# SmartSwitch2_0.net
KiCad netlist of a schematic drawn in Altium Designer
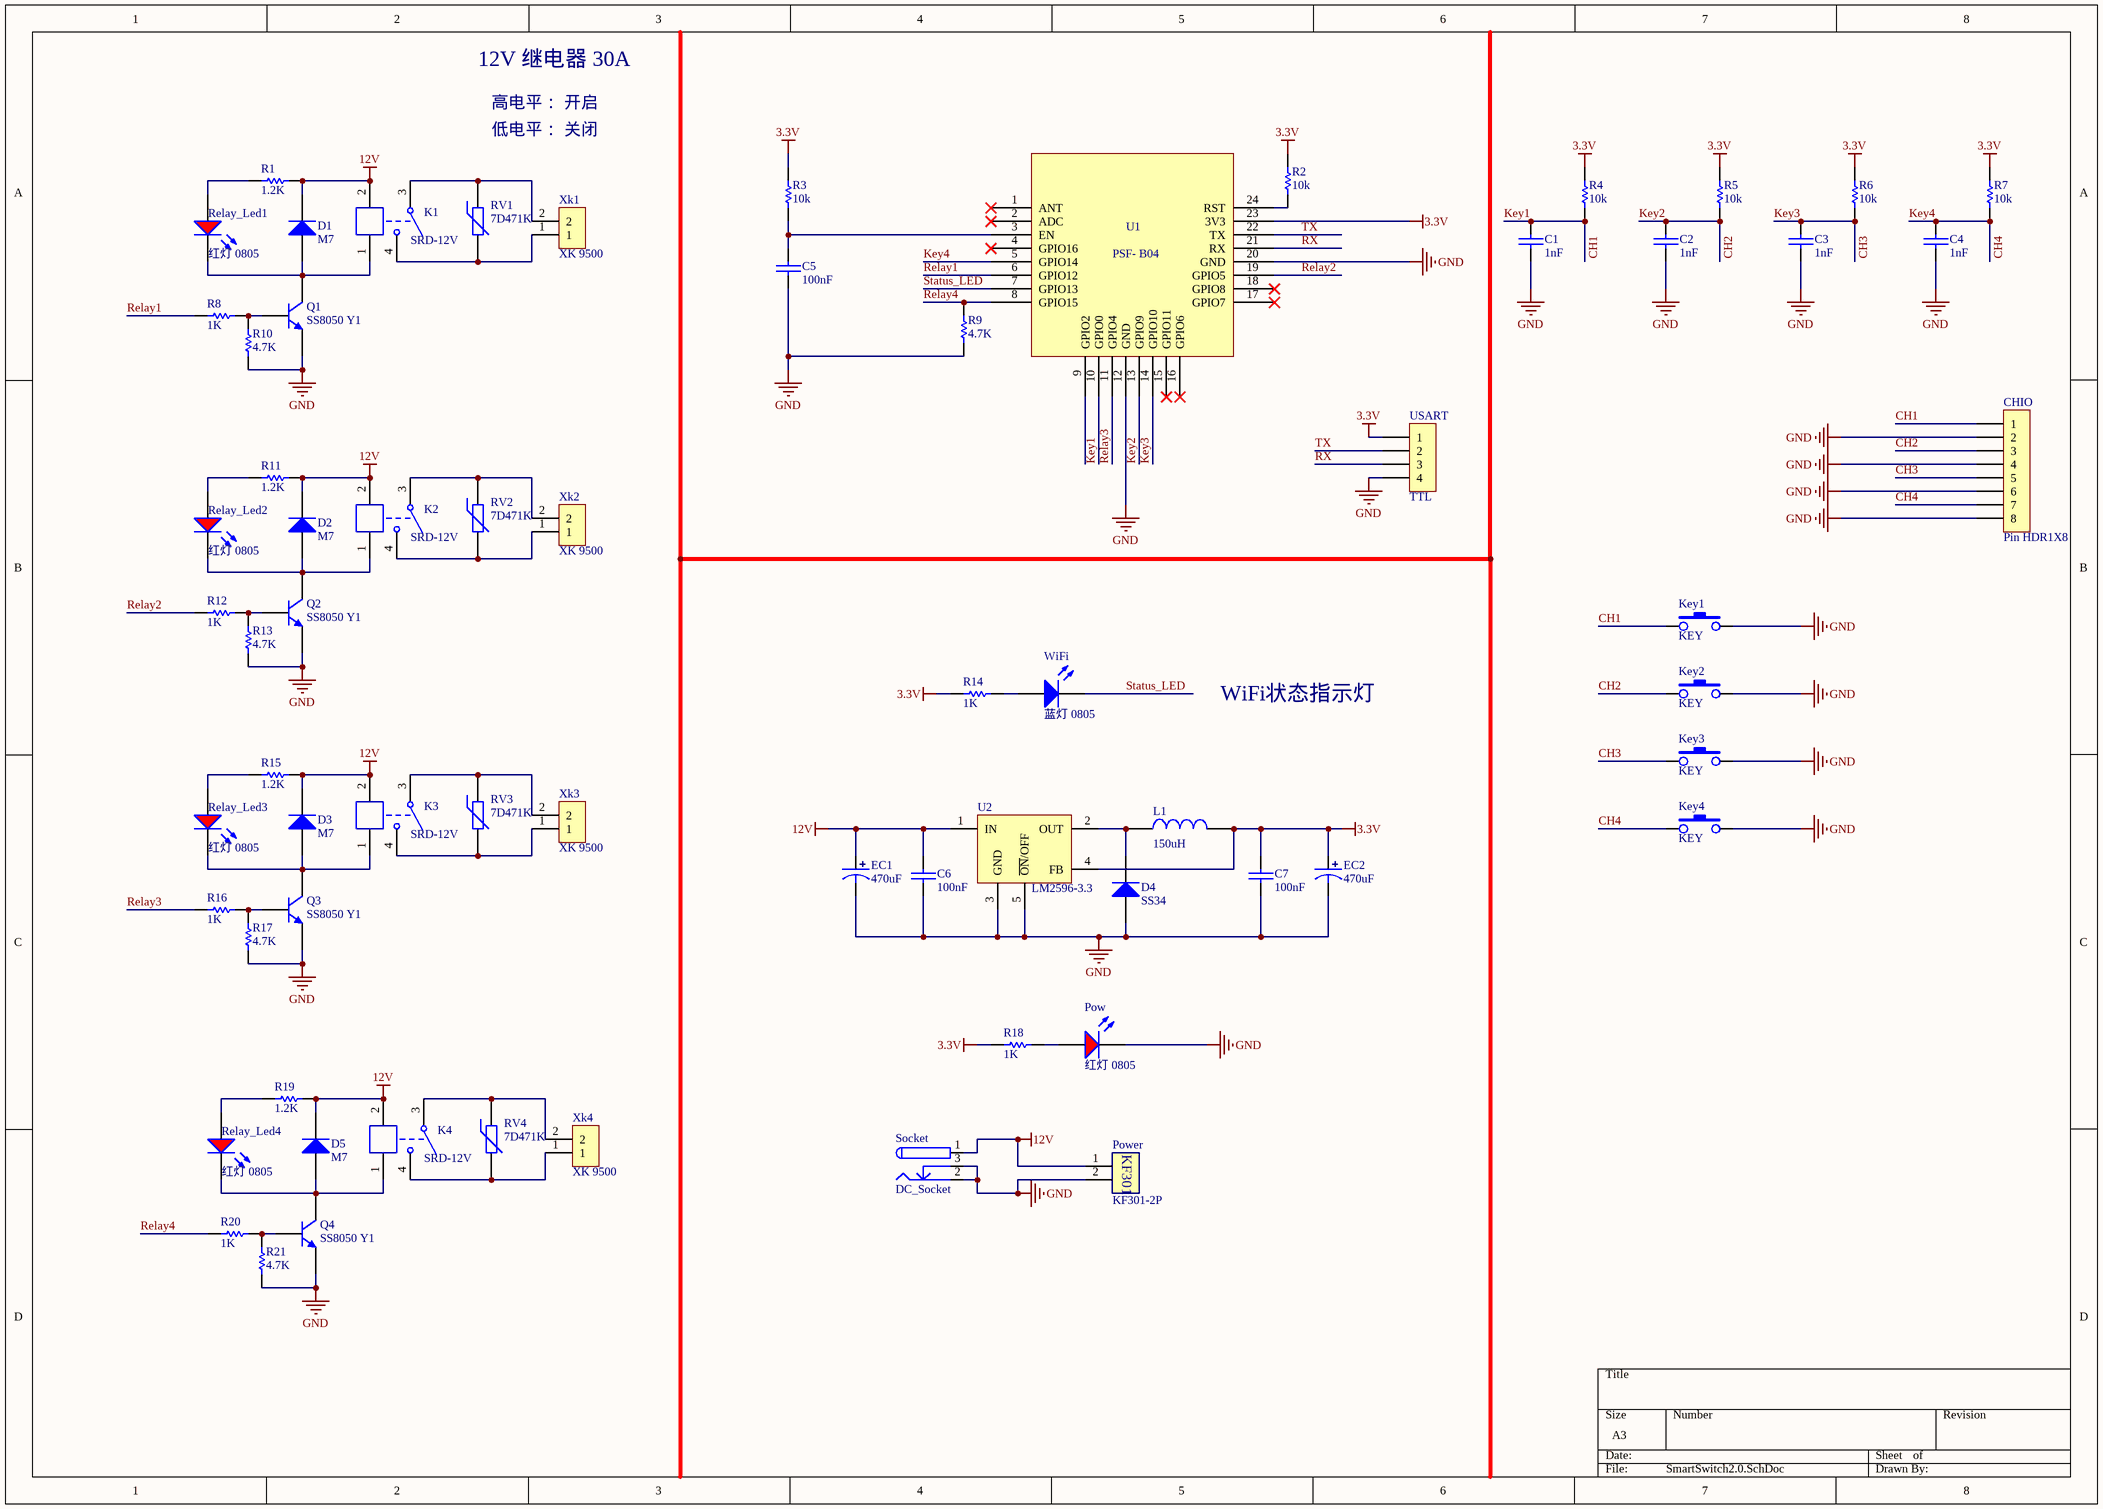
[diagram p0: SmartSwitch2.0.SchDoc]

(export (version "E")
  (design (tool "Eeschema 10.0.6"))
  (components
    (comp (ref "C1")
      (value "1nF")
      (footprint "0603C")
      (description "无极性电容")
      (libsource (lib "电容") (part "CAP"))
    )
    (comp (ref "C2")
      (value "1nF")
      (footprint "0603C")
      (description "无极性电容")
      (libsource (lib "电容") (part "CAP"))
    )
    (comp (ref "C3")
      (value "1nF")
      (footprint "0603C")
      (description "无极性电容")
      (libsource (lib "电容") (part "CAP"))
    )
    (comp (ref "C4")
      (value "1nF")
      (footprint "0603C")
      (description "无极性电容")
      (libsource (lib "电容") (part "CAP"))
    )
    (comp (ref "C5")
      (value "100nF")
      (footprint "0603C")
      (description "无极性电容")
      (libsource (lib "电容") (part "CAP"))
    )
    (comp (ref "C6")
      (value "100nF")
      (footprint "0603C")
      (description "无极性电容")
      (libsource (lib "电容") (part "CAP"))
    )
    (comp (ref "C7")
      (value "100nF")
      (footprint "0603C")
      (description "无极性电容")
      (libsource (lib "电容") (part "CAP"))
    )
    (comp (ref "CHIO")
      (value "Pin HDR1X8")
      (footprint "Pin HDR1X8/2.54mm-S")
      (libsource (lib "排针") (part "Pin HDR1X8"))
    )
    (comp (ref "D1")
      (value "M7")
      (footprint "SMA(DO-214AC)_S1")
      (description "二极管")
      (libsource (lib "Miscellaneous Devices LC") (part "SMA(DO-214AC) M7"))
    )
    (comp (ref "D2")
      (value "M7")
      (footprint "SMA(DO-214AC)_S1")
      (description "二极管")
      (libsource (lib "Miscellaneous Devices LC") (part "SMA(DO-214AC) M7"))
    )
    (comp (ref "D3")
      (value "M7")
      (footprint "SMA(DO-214AC)_S1")
      (description "二极管")
      (libsource (lib "Miscellaneous Devices LC") (part "SMA(DO-214AC) M7"))
    )
    (comp (ref "D4")
      (value "SS34")
      (footprint "SMA(DO-214AC)_S1")
      (description "二极管")
      (libsource (lib "Miscellaneous Devices LC") (part "SMA(DO-214AC) SS54"))
    )
    (comp (ref "D5")
      (value "M7")
      (footprint "SMA(DO-214AC)_S1")
      (description "二极管")
      (libsource (lib "Miscellaneous Devices LC") (part "SMA(DO-214AC) M7"))
    )
    (comp (ref "EC1")
      (value "470uF")
      (footprint "SMD-EC8X8X10")
      (description "贴片电解电容")
      (libsource (lib "电容") (part "SMD_ECAP"))
    )
    (comp (ref "EC2")
      (value "470uF")
      (footprint "SMD-EC8X8X10")
      (description "贴片电解电容")
      (libsource (lib "电容") (part "SMD_ECAP"))
    )
    (comp (ref "K1")
      (value "SRD-12V")
      (footprint "SLA-xxVDC-SL-A")
      (description "12V一组常开")
      (libsource (lib "继电器") (part "SLA-12VDC-SL-A"))
    )
    (comp (ref "K2")
      (value "SRD-12V")
      (footprint "SLA-xxVDC-SL-A")
      (description "12V一组常开")
      (libsource (lib "继电器") (part "SLA-12VDC-SL-A"))
    )
    (comp (ref "K3")
      (value "SRD-12V")
      (footprint "SLA-xxVDC-SL-A")
      (description "12V一组常开")
      (libsource (lib "继电器") (part "SLA-12VDC-SL-A"))
    )
    (comp (ref "K4")
      (value "SRD-12V")
      (footprint "SLA-xxVDC-SL-A")
      (description "12V一组常开")
      (libsource (lib "继电器") (part "SLA-12VDC-SL-A"))
    )
    (comp (ref "Key1") (value "KEY") (footprint "DIP-6X6X4.3") (libsource (lib "轻触开关") (part "KEY")))
    (comp (ref "Key2") (value "KEY") (footprint "DIP-6X6X4.3") (libsource (lib "轻触开关") (part "KEY")))
    (comp (ref "Key3") (value "KEY") (footprint "DIP-6X6X4.3") (libsource (lib "轻触开关") (part "KEY")))
    (comp (ref "Key4") (value "KEY") (footprint "DIP-6X6X4.3") (libsource (lib "轻触开关") (part "KEY")))
    (comp (ref "L1")
      (value "150uH")
      (footprint "PK0810")
      (description "INDUCTOR")
      (libsource (lib "电感") (part "INDUCTOR"))
    )
    (comp (ref "Pow")
      (value "红灯 0805")
      (footprint "0805_LED_S1")
      (description "发光二极管")
      (libsource (lib "Miscellaneous Devices LC") (part "0805 红灯"))
    )
    (comp (ref "Power")
      (value "KF301-2P")
      (footprint "KF301-5.0-2P")
      (libsource (lib "KF301") (part "KF301-2P"))
    )
    (comp (ref "Q1")
      (value "SS8050 Y1")
      (footprint "SOT-23(SOT-23-3)")
      (description "三极管")
      (libsource (lib "Miscellaneous Devices LC") (part "SOT-23 SS8050 Y1"))
    )
    (comp (ref "Q2")
      (value "SS8050 Y1")
      (footprint "SOT-23(SOT-23-3)")
      (description "三极管")
      (libsource (lib "Miscellaneous Devices LC") (part "SOT-23 SS8050 Y1"))
    )
    (comp (ref "Q3")
      (value "SS8050 Y1")
      (footprint "SOT-23(SOT-23-3)")
      (description "三极管")
      (libsource (lib "Miscellaneous Devices LC") (part "SOT-23 SS8050 Y1"))
    )
    (comp (ref "Q4")
      (value "SS8050 Y1")
      (footprint "SOT-23(SOT-23-3)")
      (description "三极管")
      (libsource (lib "Miscellaneous Devices LC") (part "SOT-23 SS8050 Y1"))
    )
    (comp (ref "R1") (value "1.2K") (footprint "0603R") (libsource (lib "电阻") (part "RES")))
    (comp (ref "R2") (value "10k") (footprint "0603R") (libsource (lib "电阻") (part "RES")))
    (comp (ref "R3") (value "10k") (footprint "0603R") (libsource (lib "电阻") (part "RES")))
    (comp (ref "R4") (value "10k") (footprint "0603R") (libsource (lib "电阻") (part "RES")))
    (comp (ref "R5") (value "10k") (footprint "0603R") (libsource (lib "电阻") (part "RES")))
    (comp (ref "R6") (value "10k") (footprint "0603R") (libsource (lib "电阻") (part "RES")))
    (comp (ref "R7") (value "10k") (footprint "0603R") (libsource (lib "电阻") (part "RES")))
    (comp (ref "R8") (value "1K") (footprint "0603R") (libsource (lib "电阻") (part "RES")))
    (comp (ref "R9") (value "4.7K") (footprint "0603R") (libsource (lib "电阻") (part "RES")))
    (comp (ref "R10") (value "4.7K") (footprint "0603R") (libsource (lib "电阻") (part "RES")))
    (comp (ref "R11") (value "1.2K") (footprint "0603R") (libsource (lib "电阻") (part "RES")))
    (comp (ref "R12") (value "1K") (footprint "0603R") (libsource (lib "电阻") (part "RES")))
    (comp (ref "R13") (value "4.7K") (footprint "0603R") (libsource (lib "电阻") (part "RES")))
    (comp (ref "R14") (value "1K") (footprint "0603R") (libsource (lib "电阻") (part "RES")))
    (comp (ref "R15") (value "1.2K") (footprint "0603R") (libsource (lib "电阻") (part "RES")))
    (comp (ref "R16") (value "1K") (footprint "0603R") (libsource (lib "电阻") (part "RES")))
    (comp (ref "R17") (value "4.7K") (footprint "0603R") (libsource (lib "电阻") (part "RES")))
    (comp (ref "R18") (value "1K") (footprint "0603R") (libsource (lib "电阻") (part "RES")))
    (comp (ref "R19") (value "1.2K") (footprint "0603R") (libsource (lib "电阻") (part "RES")))
    (comp (ref "R20") (value "1K") (footprint "0603R") (libsource (lib "电阻") (part "RES")))
    (comp (ref "R21") (value "4.7K") (footprint "0603R") (libsource (lib "电阻") (part "RES")))
    (comp (ref "Relay_Led1")
      (value "红灯 0805")
      (footprint "0805_LED_S1")
      (description "发光二极管")
      (libsource (lib "Miscellaneous Devices LC") (part "0805 红灯"))
    )
    (comp (ref "Relay_Led2")
      (value "红灯 0805")
      (footprint "0805_LED_S1")
      (description "发光二极管")
      (libsource (lib "Miscellaneous Devices LC") (part "0805 红灯"))
    )
    (comp (ref "Relay_Led3")
      (value "红灯 0805")
      (footprint "0805_LED_S1")
      (description "发光二极管")
      (libsource (lib "Miscellaneous Devices LC") (part "0805 红灯"))
    )
    (comp (ref "Relay_Led4")
      (value "红灯 0805")
      (footprint "0805_LED_S1")
      (description "发光二极管")
      (libsource (lib "Miscellaneous Devices LC") (part "0805 红灯"))
    )
    (comp (ref "RV1")
      (value "7D471K")
      (footprint "Varistor-7.5mm")
      (description "压敏电阻")
      (libsource (lib "电阻") (part "Varistor"))
    )
    (comp (ref "RV2")
      (value "7D471K")
      (footprint "Varistor-7.5mm")
      (description "压敏电阻")
      (libsource (lib "电阻") (part "Varistor"))
    )
    (comp (ref "RV3")
      (value "7D471K")
      (footprint "Varistor-7.5mm")
      (description "压敏电阻")
      (libsource (lib "电阻") (part "Varistor"))
    )
    (comp (ref "RV4")
      (value "7D471K")
      (footprint "Varistor-7.5mm")
      (description "压敏电阻")
      (libsource (lib "电阻") (part "Varistor"))
    )
    (comp (ref "Socket") (value "DC_Socket") (footprint "DC-005") (libsource (lib "电源插座") (part "DC_Socket")))
    (comp (ref "U1")
      (value "PSF- B04")
      (footprint "PSF- B04")
      (libsource (lib "my_Library") (part "PSF- B04"))
    )
    (comp (ref "U2")
      (value "LM2596-3.3")
      (footprint "TO263-5A")
      (description "DC降压芯片")
      (libsource (lib "电源芯片") (part "LM2596-3.3"))
    )
    (comp (ref "USART")
      (value "TTL")
      (footprint "Pin HDR1X4/2.54mm-S")
      (libsource (lib "排针") (part "Pin HDR1X4"))
    )
    (comp (ref "WiFi")
      (value "蓝灯 0805")
      (footprint "0805_LED_S1")
      (description "发光二极管")
      (libsource (lib "Miscellaneous Devices LC") (part "0805 蓝灯"))
    )
    (comp (ref "Xk1") (value "XK 9500") (footprint "XK 9500") (libsource (lib "my_Library") (part "XK 9500")))
    (comp (ref "Xk2") (value "XK 9500") (footprint "XK 9500") (libsource (lib "my_Library") (part "XK 9500")))
    (comp (ref "Xk3") (value "XK 9500") (footprint "XK 9500") (libsource (lib "my_Library") (part "XK 9500")))
    (comp (ref "Xk4") (value "XK 9500") (footprint "XK 9500") (libsource (lib "my_Library") (part "XK 9500")))
  )
  (nets
    (net (code "1") (name "/CH1") (class "Default")
      (node (ref "C1") (pin "2") (pinfunction "2_2") (pintype "passive"))
      (node (ref "CHIO") (pin "1") (pinfunction "1_1") (pintype "passive"))
      (node (ref "Key1") (pin "1") (pinfunction "1_1") (pintype "passive"))
      (node (ref "R4") (pin "2") (pinfunction "2_2") (pintype "passive"))
      (node (ref "U1") (pin "10") (pinfunction "GPIO0_10") (pintype "passive"))
    )
    (net (code "2") (name "/CH2") (class "Default")
      (node (ref "C2") (pin "2") (pinfunction "2_2") (pintype "passive"))
      (node (ref "CHIO") (pin "3") (pinfunction "3_3") (pintype "passive"))
      (node (ref "Key2") (pin "1") (pinfunction "1_1") (pintype "passive"))
      (node (ref "R5") (pin "2") (pinfunction "2_2") (pintype "passive"))
      (node (ref "U1") (pin "13") (pinfunction "GPIO9_13") (pintype "passive"))
    )
    (net (code "3") (name "/CH3") (class "Default")
      (node (ref "C3") (pin "2") (pinfunction "2_2") (pintype "passive"))
      (node (ref "CHIO") (pin "5") (pinfunction "5_5") (pintype "passive"))
      (node (ref "Key3") (pin "1") (pinfunction "1_1") (pintype "passive"))
      (node (ref "R6") (pin "2") (pinfunction "2_2") (pintype "passive"))
      (node (ref "U1") (pin "14") (pinfunction "GPIO10_14") (pintype "passive"))
    )
    (net (code "4") (name "/CH4") (class "Default")
      (node (ref "C4") (pin "2") (pinfunction "2_2") (pintype "passive"))
      (node (ref "CHIO") (pin "7") (pinfunction "7_7") (pintype "passive"))
      (node (ref "Key4") (pin "1") (pinfunction "1_1") (pintype "passive"))
      (node (ref "R7") (pin "2") (pinfunction "2_2") (pintype "passive"))
      (node (ref "U1") (pin "5") (pinfunction "GPIO14_5") (pintype "passive"))
    )
    (net (code "5") (name "/RX") (class "Default")
      (node (ref "U1") (pin "21") (pinfunction "RX_21") (pintype "passive"))
      (node (ref "USART") (pin "3") (pinfunction "3_3") (pintype "passive"))
    )
    (net (code "6") (name "/Relay1") (class "Default")
      (node (ref "R8") (pin "1") (pinfunction "1_1") (pintype "passive"))
      (node (ref "U1") (pin "6") (pinfunction "GPIO12_6") (pintype "passive"))
    )
    (net (code "7") (name "/Relay2") (class "Default")
      (node (ref "R12") (pin "1") (pinfunction "1_1") (pintype "passive"))
      (node (ref "U1") (pin "19") (pinfunction "GPIO5_19") (pintype "passive"))
    )
    (net (code "8") (name "/Relay3") (class "Default")
      (node (ref "R16") (pin "1") (pinfunction "1_1") (pintype "passive"))
      (node (ref "U1") (pin "11") (pinfunction "GPIO4_11") (pintype "passive"))
    )
    (net (code "9") (name "/Relay4") (class "Default")
      (node (ref "R20") (pin "1") (pinfunction "1_1") (pintype "passive"))
      (node (ref "R9") (pin "2") (pinfunction "2_2") (pintype "passive"))
      (node (ref "U1") (pin "8") (pinfunction "GPIO15_8") (pintype "passive"))
    )
    (net (code "10") (name "/Status_LED") (class "Default")
      (node (ref "U1") (pin "7") (pinfunction "GPIO13_7") (pintype "passive"))
      (node (ref "WiFi") (pin "K") (pinfunction "K_K") (pintype "passive"))
    )
    (net (code "11") (name "/TX") (class "Default")
      (node (ref "U1") (pin "22") (pinfunction "TX_22") (pintype "passive"))
      (node (ref "USART") (pin "2") (pinfunction "2_2") (pintype "passive"))
    )
    (net (code "12") (name "3.3V") (class "Default")
      (node (ref "C7") (pin "2") (pinfunction "2_2") (pintype "passive"))
      (node (ref "EC2") (pin "1") (pinfunction "1_1") (pintype "passive"))
      (node (ref "L1") (pin "2") (pinfunction "2_2") (pintype "passive"))
      (node (ref "R14") (pin "1") (pinfunction "1_1") (pintype "passive"))
      (node (ref "R18") (pin "1") (pinfunction "1_1") (pintype "passive"))
      (node (ref "R2") (pin "1") (pinfunction "1_1") (pintype "passive"))
      (node (ref "R3") (pin "2") (pinfunction "2_2") (pintype "passive"))
      (node (ref "R4") (pin "1") (pinfunction "1_1") (pintype "passive"))
      (node (ref "R5") (pin "1") (pinfunction "1_1") (pintype "passive"))
      (node (ref "R6") (pin "1") (pinfunction "1_1") (pintype "passive"))
      (node (ref "R7") (pin "1") (pinfunction "1_1") (pintype "passive"))
      (node (ref "U1") (pin "23") (pinfunction "3V3_23") (pintype "passive"))
      (node (ref "U2") (pin "4") (pinfunction "FB_4") (pintype "passive"))
      (node (ref "USART") (pin "1") (pinfunction "1_1") (pintype "passive"))
    )
    (net (code "13") (name "12V") (class "Default")
      (node (ref "C6") (pin "2") (pinfunction "2_2") (pintype "passive"))
      (node (ref "D1") (pin "2") (pinfunction "K_2") (pintype "passive"))
      (node (ref "D2") (pin "2") (pinfunction "K_2") (pintype "passive"))
      (node (ref "D3") (pin "2") (pinfunction "K_2") (pintype "passive"))
      (node (ref "D5") (pin "2") (pinfunction "K_2") (pintype "passive"))
      (node (ref "EC1") (pin "1") (pinfunction "1_1") (pintype "passive"))
      (node (ref "K1") (pin "2") (pinfunction "2_2") (pintype "passive"))
      (node (ref "K2") (pin "2") (pinfunction "2_2") (pintype "passive"))
      (node (ref "K3") (pin "2") (pinfunction "2_2") (pintype "passive"))
      (node (ref "K4") (pin "2") (pinfunction "2_2") (pintype "passive"))
      (node (ref "Power") (pin "1") (pinfunction "1_1") (pintype "passive"))
      (node (ref "R1") (pin "1") (pinfunction "1_1") (pintype "passive"))
      (node (ref "R11") (pin "1") (pinfunction "1_1") (pintype "passive"))
      (node (ref "R15") (pin "1") (pinfunction "1_1") (pintype "passive"))
      (node (ref "R19") (pin "1") (pinfunction "1_1") (pintype "passive"))
      (node (ref "Socket") (pin "1") (pinfunction "1_1") (pintype "power_in"))
      (node (ref "U2") (pin "1") (pinfunction "IN_1") (pintype "power_in"))
    )
    (net (code "14") (name "GND") (class "Default")
      (node (ref "C1") (pin "1") (pinfunction "1_1") (pintype "passive"))
      (node (ref "C2") (pin "1") (pinfunction "1_1") (pintype "passive"))
      (node (ref "C3") (pin "1") (pinfunction "1_1") (pintype "passive"))
      (node (ref "C4") (pin "1") (pinfunction "1_1") (pintype "passive"))
      (node (ref "C5") (pin "1") (pinfunction "1_1") (pintype "passive"))
      (node (ref "C6") (pin "1") (pinfunction "1_1") (pintype "passive"))
      (node (ref "C7") (pin "1") (pinfunction "1_1") (pintype "passive"))
      (node (ref "CHIO") (pin "2") (pinfunction "2_2") (pintype "passive"))
      (node (ref "CHIO") (pin "4") (pinfunction "4_4") (pintype "passive"))
      (node (ref "CHIO") (pin "6") (pinfunction "6_6") (pintype "passive"))
      (node (ref "CHIO") (pin "8") (pinfunction "8_8") (pintype "passive"))
      (node (ref "D4") (pin "1") (pinfunction "A_1") (pintype "passive"))
      (node (ref "EC1") (pin "2") (pinfunction "2_2") (pintype "passive"))
      (node (ref "EC2") (pin "2") (pinfunction "2_2") (pintype "passive"))
      (node (ref "Key1") (pin "3") (pinfunction "3_3") (pintype "passive"))
      (node (ref "Key2") (pin "3") (pinfunction "3_3") (pintype "passive"))
      (node (ref "Key3") (pin "3") (pinfunction "3_3") (pintype "passive"))
      (node (ref "Key4") (pin "3") (pinfunction "3_3") (pintype "passive"))
      (node (ref "Pow") (pin "K") (pinfunction "K_K") (pintype "passive"))
      (node (ref "Power") (pin "2") (pinfunction "2_2") (pintype "passive"))
      (node (ref "Q1") (pin "2") (pinfunction "E_2") (pintype "passive"))
      (node (ref "Q2") (pin "2") (pinfunction "E_2") (pintype "passive"))
      (node (ref "Q3") (pin "2") (pinfunction "E_2") (pintype "passive"))
      (node (ref "Q4") (pin "2") (pinfunction "E_2") (pintype "passive"))
      (node (ref "R10") (pin "1") (pinfunction "1_1") (pintype "passive"))
      (node (ref "R13") (pin "1") (pinfunction "1_1") (pintype "passive"))
      (node (ref "R17") (pin "1") (pinfunction "1_1") (pintype "passive"))
      (node (ref "R21") (pin "1") (pinfunction "1_1") (pintype "passive"))
      (node (ref "R9") (pin "1") (pinfunction "1_1") (pintype "passive"))
      (node (ref "Socket") (pin "2") (pinfunction "2_2") (pintype "power_in"))
      (node (ref "Socket") (pin "3") (pinfunction "3_3") (pintype "power_in"))
      (node (ref "U1") (pin "12") (pinfunction "GND_12") (pintype "passive"))
      (node (ref "U1") (pin "20") (pinfunction "GND_20") (pintype "passive"))
      (node (ref "U2") (pin "3") (pinfunction "GND_3") (pintype "power_in"))
      (node (ref "U2") (pin "5") (pinfunction "~{ON}/OFF_5") (pintype "passive"))
      (node (ref "USART") (pin "4") (pinfunction "4_4") (pintype "passive"))
    )
    (net (code "15") (name "Net-(D1-A)") (class "Default")
      (node (ref "D1") (pin "1") (pinfunction "A_1") (pintype "passive"))
      (node (ref "K1") (pin "1") (pinfunction "1_1") (pintype "passive"))
      (node (ref "Q1") (pin "3") (pinfunction "C_3") (pintype "passive"))
      (node (ref "Relay_Led1") (pin "K") (pinfunction "K_K") (pintype "passive"))
    )
    (net (code "16") (name "Net-(D2-A)") (class "Default")
      (node (ref "D2") (pin "1") (pinfunction "A_1") (pintype "passive"))
      (node (ref "K2") (pin "1") (pinfunction "1_1") (pintype "passive"))
      (node (ref "Q2") (pin "3") (pinfunction "C_3") (pintype "passive"))
      (node (ref "Relay_Led2") (pin "K") (pinfunction "K_K") (pintype "passive"))
    )
    (net (code "17") (name "Net-(D3-A)") (class "Default")
      (node (ref "D3") (pin "1") (pinfunction "A_1") (pintype "passive"))
      (node (ref "K3") (pin "1") (pinfunction "1_1") (pintype "passive"))
      (node (ref "Q3") (pin "3") (pinfunction "C_3") (pintype "passive"))
      (node (ref "Relay_Led3") (pin "K") (pinfunction "K_K") (pintype "passive"))
    )
    (net (code "18") (name "Net-(D4-K)") (class "Default")
      (node (ref "D4") (pin "2") (pinfunction "K_2") (pintype "passive"))
      (node (ref "L1") (pin "1") (pinfunction "1_1") (pintype "passive"))
      (node (ref "U2") (pin "2") (pinfunction "OUT_2") (pintype "power_in"))
    )
    (net (code "19") (name "Net-(D5-A)") (class "Default")
      (node (ref "D5") (pin "1") (pinfunction "A_1") (pintype "passive"))
      (node (ref "K4") (pin "1") (pinfunction "1_1") (pintype "passive"))
      (node (ref "Q4") (pin "3") (pinfunction "C_3") (pintype "passive"))
      (node (ref "Relay_Led4") (pin "K") (pinfunction "K_K") (pintype "passive"))
    )
    (net (code "20") (name "Net-(K1-Pad3)") (class "Default")
      (node (ref "K1") (pin "3") (pinfunction "3_3") (pintype "passive"))
      (node (ref "RV1") (pin "1") (pinfunction "1_1") (pintype "passive"))
      (node (ref "Xk1") (pin "2") (pinfunction "2_2") (pintype "passive"))
    )
    (net (code "21") (name "Net-(K1-Pad4)") (class "Default")
      (node (ref "K1") (pin "4") (pinfunction "4_4") (pintype "passive"))
      (node (ref "RV1") (pin "2") (pinfunction "2_2") (pintype "passive"))
      (node (ref "Xk1") (pin "1") (pinfunction "1_1") (pintype "passive"))
    )
    (net (code "22") (name "Net-(K2-Pad3)") (class "Default")
      (node (ref "K2") (pin "3") (pinfunction "3_3") (pintype "passive"))
      (node (ref "RV2") (pin "1") (pinfunction "1_1") (pintype "passive"))
      (node (ref "Xk2") (pin "2") (pinfunction "2_2") (pintype "passive"))
    )
    (net (code "23") (name "Net-(K2-Pad4)") (class "Default")
      (node (ref "K2") (pin "4") (pinfunction "4_4") (pintype "passive"))
      (node (ref "RV2") (pin "2") (pinfunction "2_2") (pintype "passive"))
      (node (ref "Xk2") (pin "1") (pinfunction "1_1") (pintype "passive"))
    )
    (net (code "24") (name "Net-(K3-Pad3)") (class "Default")
      (node (ref "K3") (pin "3") (pinfunction "3_3") (pintype "passive"))
      (node (ref "RV3") (pin "1") (pinfunction "1_1") (pintype "passive"))
      (node (ref "Xk3") (pin "2") (pinfunction "2_2") (pintype "passive"))
    )
    (net (code "25") (name "Net-(K3-Pad4)") (class "Default")
      (node (ref "K3") (pin "4") (pinfunction "4_4") (pintype "passive"))
      (node (ref "RV3") (pin "2") (pinfunction "2_2") (pintype "passive"))
      (node (ref "Xk3") (pin "1") (pinfunction "1_1") (pintype "passive"))
    )
    (net (code "26") (name "Net-(K4-Pad3)") (class "Default")
      (node (ref "K4") (pin "3") (pinfunction "3_3") (pintype "passive"))
      (node (ref "RV4") (pin "1") (pinfunction "1_1") (pintype "passive"))
      (node (ref "Xk4") (pin "2") (pinfunction "2_2") (pintype "passive"))
    )
    (net (code "27") (name "Net-(K4-Pad4)") (class "Default")
      (node (ref "K4") (pin "4") (pinfunction "4_4") (pintype "passive"))
      (node (ref "RV4") (pin "2") (pinfunction "2_2") (pintype "passive"))
      (node (ref "Xk4") (pin "1") (pinfunction "1_1") (pintype "passive"))
    )
    (net (code "28") (name "Net-(Pow-PadA)") (class "Default")
      (node (ref "Pow") (pin "A") (pinfunction "A_A") (pintype "passive"))
      (node (ref "R18") (pin "2") (pinfunction "2_2") (pintype "passive"))
    )
    (net (code "29") (name "Net-(Q1-B)") (class "Default")
      (node (ref "Q1") (pin "1") (pinfunction "B_1") (pintype "passive"))
      (node (ref "R10") (pin "2") (pinfunction "2_2") (pintype "passive"))
      (node (ref "R8") (pin "2") (pinfunction "2_2") (pintype "passive"))
    )
    (net (code "30") (name "Net-(Q2-B)") (class "Default")
      (node (ref "Q2") (pin "1") (pinfunction "B_1") (pintype "passive"))
      (node (ref "R12") (pin "2") (pinfunction "2_2") (pintype "passive"))
      (node (ref "R13") (pin "2") (pinfunction "2_2") (pintype "passive"))
    )
    (net (code "31") (name "Net-(Q3-B)") (class "Default")
      (node (ref "Q3") (pin "1") (pinfunction "B_1") (pintype "passive"))
      (node (ref "R16") (pin "2") (pinfunction "2_2") (pintype "passive"))
      (node (ref "R17") (pin "2") (pinfunction "2_2") (pintype "passive"))
    )
    (net (code "32") (name "Net-(Q4-B)") (class "Default")
      (node (ref "Q4") (pin "1") (pinfunction "B_1") (pintype "passive"))
      (node (ref "R20") (pin "2") (pinfunction "2_2") (pintype "passive"))
      (node (ref "R21") (pin "2") (pinfunction "2_2") (pintype "passive"))
    )
    (net (code "33") (name "Net-(R1-Pad2)") (class "Default")
      (node (ref "R1") (pin "2") (pinfunction "2_2") (pintype "passive"))
      (node (ref "Relay_Led1") (pin "A") (pinfunction "A_A") (pintype "passive"))
    )
    (net (code "34") (name "Net-(R11-Pad2)") (class "Default")
      (node (ref "R11") (pin "2") (pinfunction "2_2") (pintype "passive"))
      (node (ref "Relay_Led2") (pin "A") (pinfunction "A_A") (pintype "passive"))
    )
    (net (code "35") (name "Net-(R14-Pad2)") (class "Default")
      (node (ref "R14") (pin "2") (pinfunction "2_2") (pintype "passive"))
      (node (ref "WiFi") (pin "A") (pinfunction "A_A") (pintype "passive"))
    )
    (net (code "36") (name "Net-(R15-Pad2)") (class "Default")
      (node (ref "R15") (pin "2") (pinfunction "2_2") (pintype "passive"))
      (node (ref "Relay_Led3") (pin "A") (pinfunction "A_A") (pintype "passive"))
    )
    (net (code "37") (name "Net-(R19-Pad2)") (class "Default")
      (node (ref "R19") (pin "2") (pinfunction "2_2") (pintype "passive"))
      (node (ref "Relay_Led4") (pin "A") (pinfunction "A_A") (pintype "passive"))
    )
    (net (code "38") (name "Net-(U1-EN)") (class "Default")
      (node (ref "C5") (pin "2") (pinfunction "2_2") (pintype "passive"))
      (node (ref "R3") (pin "1") (pinfunction "1_1") (pintype "passive"))
      (node (ref "U1") (pin "3") (pinfunction "EN_3") (pintype "passive"))
    )
    (net (code "39") (name "Net-(U1-RST)") (class "Default")
      (node (ref "R2") (pin "2") (pinfunction "2_2") (pintype "passive"))
      (node (ref "U1") (pin "24") (pinfunction "RST_24") (pintype "passive"))
    )
    (net (code "40") (name "unconnected-(U1-ADC-Pad2)") (class "Default")
      (node (ref "U1") (pin "2") (pinfunction "ADC_2") (pintype "passive+no_connect"))
    )
    (net (code "41") (name "unconnected-(U1-ANT-Pad1)") (class "Default")
      (node (ref "U1") (pin "1") (pinfunction "ANT_1") (pintype "passive+no_connect"))
    )
    (net (code "42") (name "unconnected-(U1-GPIO2-Pad9)") (class "Default")
      (node (ref "U1") (pin "9") (pinfunction "GPIO2_9") (pintype "passive"))
    )
    (net (code "43") (name "unconnected-(U1-GPIO6-Pad16)") (class "Default")
      (node (ref "U1") (pin "16") (pinfunction "GPIO6_16") (pintype "passive+no_connect"))
    )
    (net (code "44") (name "unconnected-(U1-GPIO7-Pad17)") (class "Default")
      (node (ref "U1") (pin "17") (pinfunction "GPIO7_17") (pintype "passive+no_connect"))
    )
    (net (code "45") (name "unconnected-(U1-GPIO8-Pad18)") (class "Default")
      (node (ref "U1") (pin "18") (pinfunction "GPIO8_18") (pintype "passive+no_connect"))
    )
    (net (code "46") (name "unconnected-(U1-GPIO11-Pad15)") (class "Default")
      (node (ref "U1") (pin "15") (pinfunction "GPIO11_15") (pintype "passive+no_connect"))
    )
    (net (code "47") (name "unconnected-(U1-GPIO16-Pad4)") (class "Default")
      (node (ref "U1") (pin "4") (pinfunction "GPIO16_4") (pintype "passive+no_connect"))
    )
  )
)
